# hexp-001.net
KiCad netlist of a schematic drawn in EAGLE
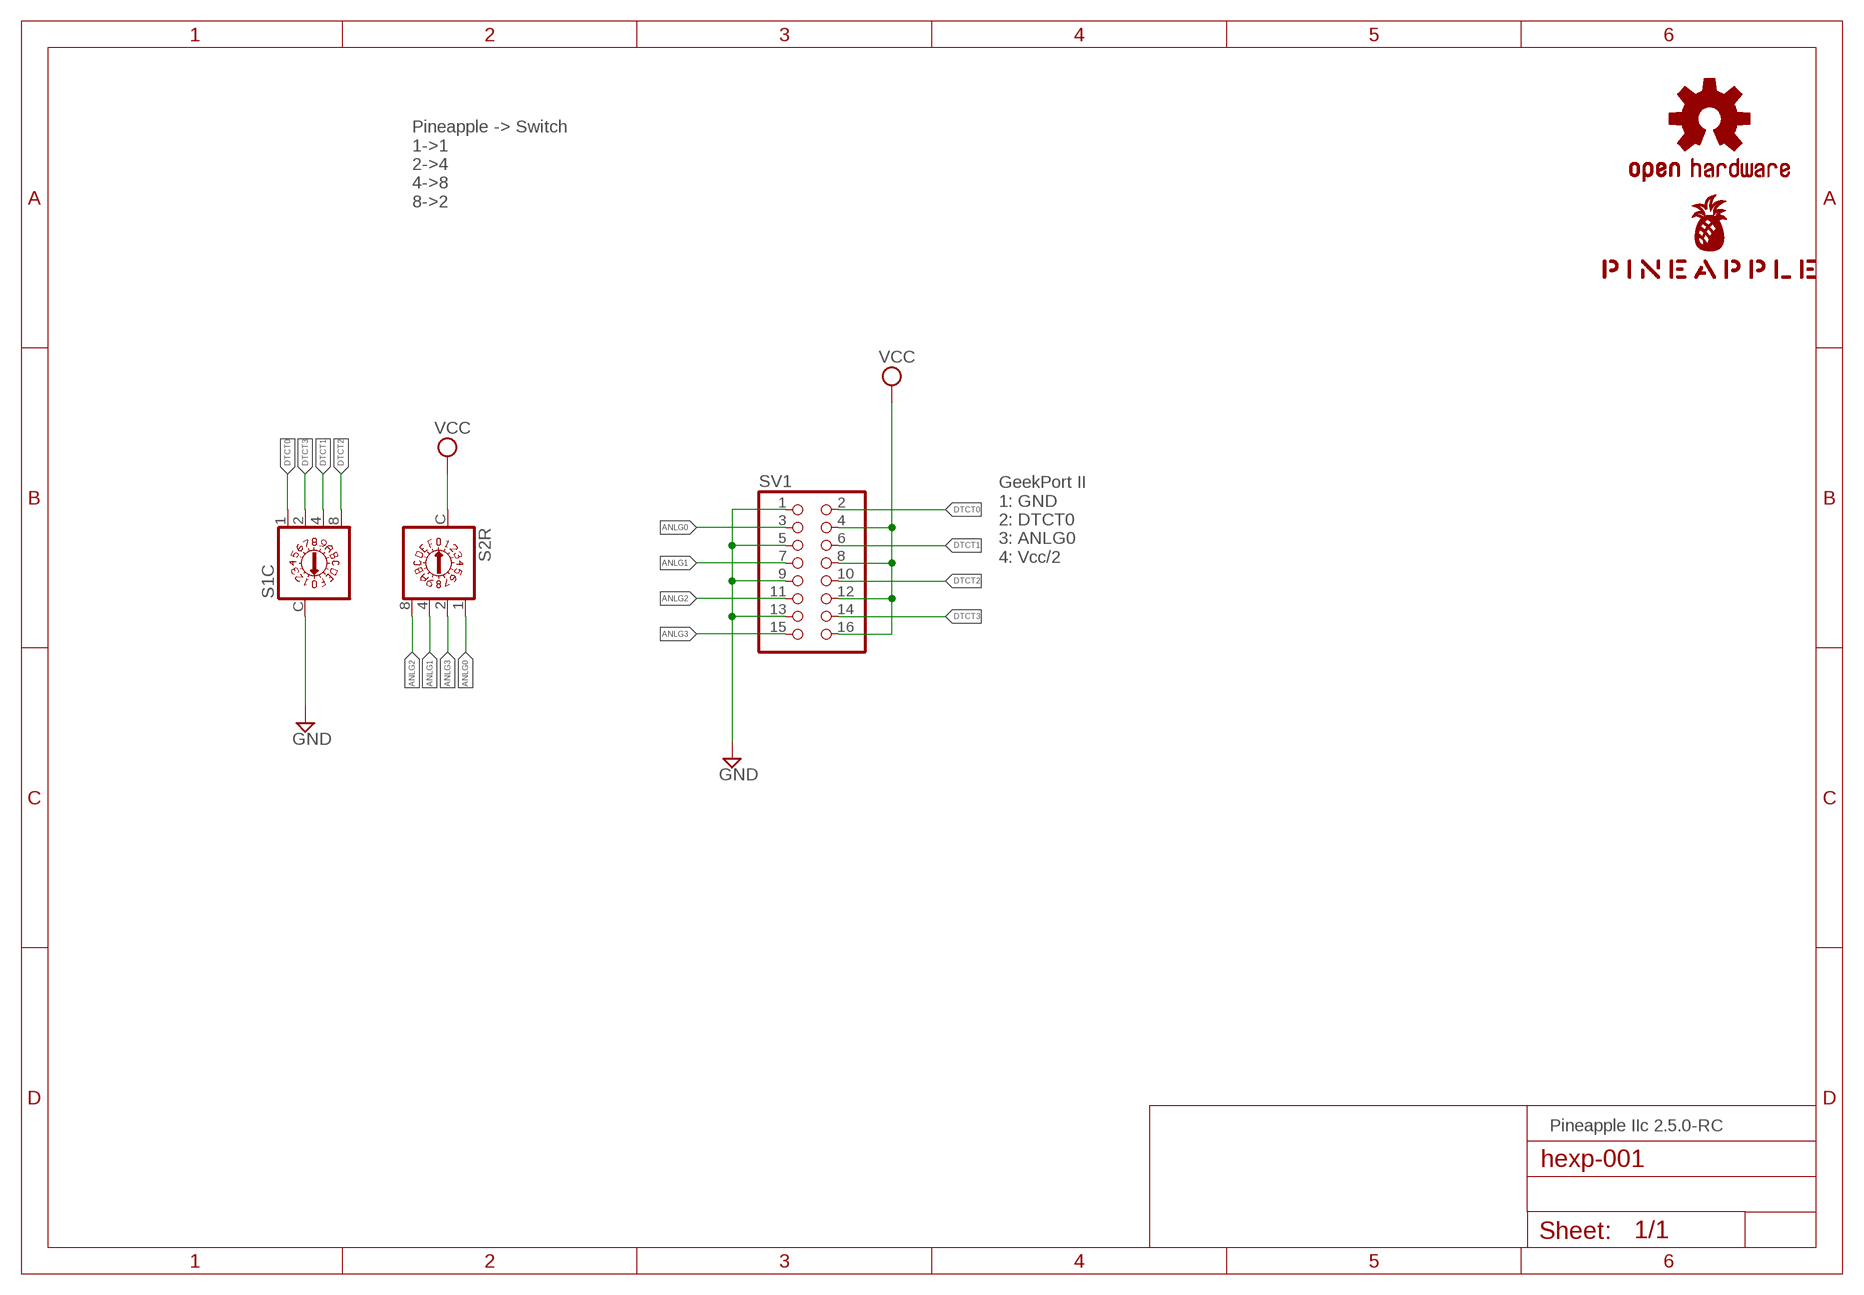
[diagram p0: schematic, sheet 1]

(export (version "E")
  (design (tool "Eeschema 10.0.6"))
  (components
    (comp (ref "LOGO1")
      (value "OSHW-LOGOS-COPPER")
      (footprint "eagle-import:OSHW-LOGO-S_COPPER")
      (libsource (lib "eagle-import") (part "OSHW-LOGOS-COPPER"))
    )
    (comp (ref "S1C")
      (value "A1353HEX")
      (footprint "eagle-import:A1353HEX")
      (libsource (lib "eagle-import") (part "A1353HEX"))
    )
    (comp (ref "S2R")
      (value "A1353HEX")
      (footprint "eagle-import:A1353HEX")
      (libsource (lib "eagle-import") (part "A1353HEX"))
    )
    (comp (ref "SV1")
      (value "PINHD-2X8")
      (footprint "eagle-import:2X08")
      (libsource (lib "eagle-import") (part "PINHD-2X8"))
    )
    (comp (ref "U$1")
      (value "PINEAPPLE450_SILK")
      (footprint "eagle-import:PINEAPPLE450_SILK")
      (libsource (lib "eagle-import") (part "PINEAPPLE450_SILK"))
    )
  )
  (nets
    (net (code "1") (name "ANLG0") (class "Default")
      (node (ref "S2R") (pin "1") (pinfunction "1_1") (pintype "passive"))
      (node (ref "SV1") (pin "3") (pinfunction "3_3") (pintype "passive"))
    )
    (net (code "2") (name "ANLG1") (class "Default")
      (node (ref "S2R") (pin "4") (pinfunction "4_4") (pintype "passive"))
      (node (ref "SV1") (pin "7") (pinfunction "7_7") (pintype "passive"))
    )
    (net (code "3") (name "ANLG2") (class "Default")
      (node (ref "S2R") (pin "8") (pinfunction "8_8") (pintype "passive"))
      (node (ref "SV1") (pin "11") (pinfunction "11_11") (pintype "passive"))
    )
    (net (code "4") (name "ANLG3") (class "Default")
      (node (ref "S2R") (pin "2") (pinfunction "2_2") (pintype "passive"))
      (node (ref "SV1") (pin "15") (pinfunction "15_15") (pintype "passive"))
    )
    (net (code "5") (name "DTCT0") (class "Default")
      (node (ref "S1C") (pin "1") (pinfunction "1_1") (pintype "passive"))
      (node (ref "SV1") (pin "2") (pinfunction "2_2") (pintype "passive"))
    )
    (net (code "6") (name "DTCT1") (class "Default")
      (node (ref "S1C") (pin "4") (pinfunction "4_4") (pintype "passive"))
      (node (ref "SV1") (pin "6") (pinfunction "6_6") (pintype "passive"))
    )
    (net (code "7") (name "DTCT2") (class "Default")
      (node (ref "S1C") (pin "8") (pinfunction "8_8") (pintype "passive"))
      (node (ref "SV1") (pin "10") (pinfunction "10_10") (pintype "passive"))
    )
    (net (code "8") (name "DTCT3") (class "Default")
      (node (ref "S1C") (pin "2") (pinfunction "2_2") (pintype "passive"))
      (node (ref "SV1") (pin "14") (pinfunction "14_14") (pintype "passive"))
    )
    (net (code "9") (name "GND") (class "Default")
      (node (ref "S1C") (pin "C") (pinfunction "C_C") (pintype "passive"))
      (node (ref "SV1") (pin "1") (pinfunction "1_1") (pintype "passive"))
      (node (ref "SV1") (pin "13") (pinfunction "13_13") (pintype "passive"))
      (node (ref "SV1") (pin "5") (pinfunction "5_5") (pintype "passive"))
      (node (ref "SV1") (pin "9") (pinfunction "9_9") (pintype "passive"))
    )
    (net (code "10") (name "VCC") (class "Default")
      (node (ref "S2R") (pin "C") (pinfunction "C_C") (pintype "passive"))
      (node (ref "SV1") (pin "12") (pinfunction "12_12") (pintype "passive"))
      (node (ref "SV1") (pin "16") (pinfunction "16_16") (pintype "passive"))
      (node (ref "SV1") (pin "4") (pinfunction "4_4") (pintype "passive"))
      (node (ref "SV1") (pin "8") (pinfunction "8_8") (pintype "passive"))
    )
  )
)
